# Debug_LEDs.net
KiCad netlist of a schematic drawn in Altium Designer
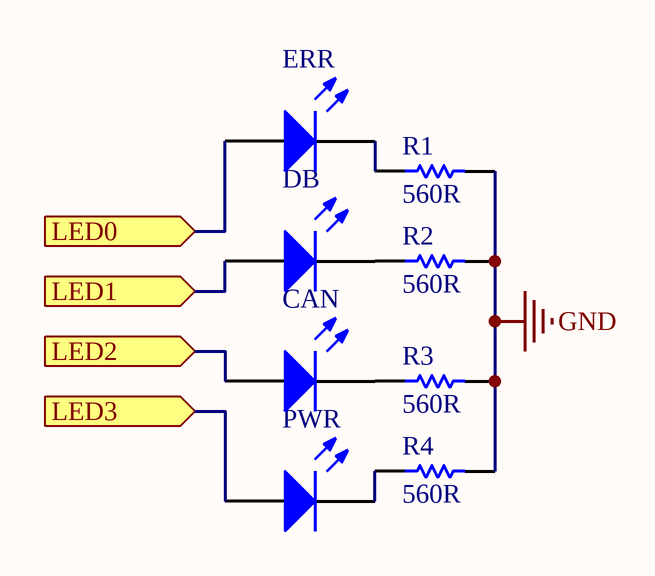
[diagram p0: Debug LEDs.SchDoc]

(export (version "E")
  (design (tool "Eeschema 10.0.6"))
  (components
    (comp (ref "CAN")
      (value "150080BS75000")
      (footprint "0805_A")
      (description "SMD mono-color Chip LED, WL-SMCW, Blue")
      (fields (field (name "MANUFACTURER") "Wuerth Elektronik"))
      (libsource (lib "Altium Content Vault") (part "WE-LED_K1A2-2"))
    )
    (comp (ref "DB")
      (value "150080GS75000")
      (footprint "0805_A")
      (description "SMD mono-color Chip LED, WL-SMCW, Green")
      (fields (field (name "MANUFACTURER") "Wuerth Elektronik"))
      (libsource (lib "Altium Content Vault") (part "WE-LED_K1A2-2"))
    )
    (comp (ref "ERR")
      (value "150080RS75000")
      (footprint "0805_A")
      (description "SMD mono-color Chip LED, WL-SMCW, Red")
      (fields (field (name "MANUFACTURER") "Wuerth Elektronik"))
      (libsource (lib "Altium Content Vault") (part "WE-LED_K1A2-2"))
    )
    (comp (ref "PWR")
      (value "150080YS75000")
      (footprint "0805_A")
      (description "SMD mono-color Chip LED, WL-SMCW, Yellow")
      (fields (field (name "MANUFACTURER") "Wuerth Elektronik"))
      (libsource (lib "Altium Content Vault") (part "WE-LED_K1A2-2"))
    )
    (comp (ref "R1")
      (value "560R")
      (footprint "RESC0805(2012)_M")
      (description "560R 0.125W 1% 0805 (2012 Metric)  SMD")
      (fields (field (name "TOLERANCE") "1 %") (field (name "POWER") "0.125 W"))
      (libsource (lib "Altium Content Vault") (part "RES"))
    )
    (comp (ref "R2")
      (value "560R")
      (footprint "RESC0805(2012)_M")
      (description "560R 0.125W 1% 0805 (2012 Metric)  SMD")
      (fields (field (name "TOLERANCE") "1 %") (field (name "POWER") "0.125 W"))
      (libsource (lib "Altium Content Vault") (part "RES"))
    )
    (comp (ref "R3")
      (value "560R")
      (footprint "RESC0805(2012)_M")
      (description "560R 0.125W 1% 0805 (2012 Metric)  SMD")
      (fields (field (name "TOLERANCE") "1 %") (field (name "POWER") "0.125 W"))
      (libsource (lib "Altium Content Vault") (part "RES"))
    )
    (comp (ref "R4")
      (value "560R")
      (footprint "RESC0805(2012)_M")
      (description "560R 0.125W 1% 0805 (2012 Metric)  SMD")
      (fields (field (name "TOLERANCE") "1 %") (field (name "POWER") "0.125 W"))
      (libsource (lib "Altium Content Vault") (part "RES"))
    )
  )
  (nets
    (net (code "1") (name "/LED0") (class "Default")
      (node (ref "ERR") (pin "2") (pinfunction "A_2") (pintype "passive"))
    )
    (net (code "2") (name "/LED1") (class "Default")
      (node (ref "DB") (pin "2") (pinfunction "A_2") (pintype "passive"))
    )
    (net (code "3") (name "/LED2") (class "Default")
      (node (ref "CAN") (pin "2") (pinfunction "A_2") (pintype "passive"))
    )
    (net (code "4") (name "/LED3") (class "Default")
      (node (ref "PWR") (pin "2") (pinfunction "A_2") (pintype "passive"))
    )
    (net (code "5") (name "GND") (class "Default")
      (node (ref "R1") (pin "2") (pinfunction "2_2") (pintype "passive"))
      (node (ref "R2") (pin "2") (pinfunction "2_2") (pintype "passive"))
      (node (ref "R3") (pin "2") (pinfunction "2_2") (pintype "passive"))
      (node (ref "R4") (pin "2") (pinfunction "2_2") (pintype "passive"))
    )
    (net (code "6") (name "Net-(CAN-K)") (class "Default")
      (node (ref "CAN") (pin "1") (pinfunction "K_1") (pintype "passive"))
      (node (ref "R3") (pin "1") (pinfunction "1_1") (pintype "passive"))
    )
    (net (code "7") (name "Net-(DB-K)") (class "Default")
      (node (ref "DB") (pin "1") (pinfunction "K_1") (pintype "passive"))
      (node (ref "R2") (pin "1") (pinfunction "1_1") (pintype "passive"))
    )
    (net (code "8") (name "Net-(ERR-K)") (class "Default")
      (node (ref "ERR") (pin "1") (pinfunction "K_1") (pintype "passive"))
      (node (ref "R1") (pin "1") (pinfunction "1_1") (pintype "passive"))
    )
    (net (code "9") (name "Net-(PWR-K)") (class "Default")
      (node (ref "PWR") (pin "1") (pinfunction "K_1") (pintype "passive"))
      (node (ref "R4") (pin "1") (pinfunction "1_1") (pintype "passive"))
    )
  )
)
